# pycom_weather_station_pcb.net
KiCad netlist of a schematic drawn in EAGLE
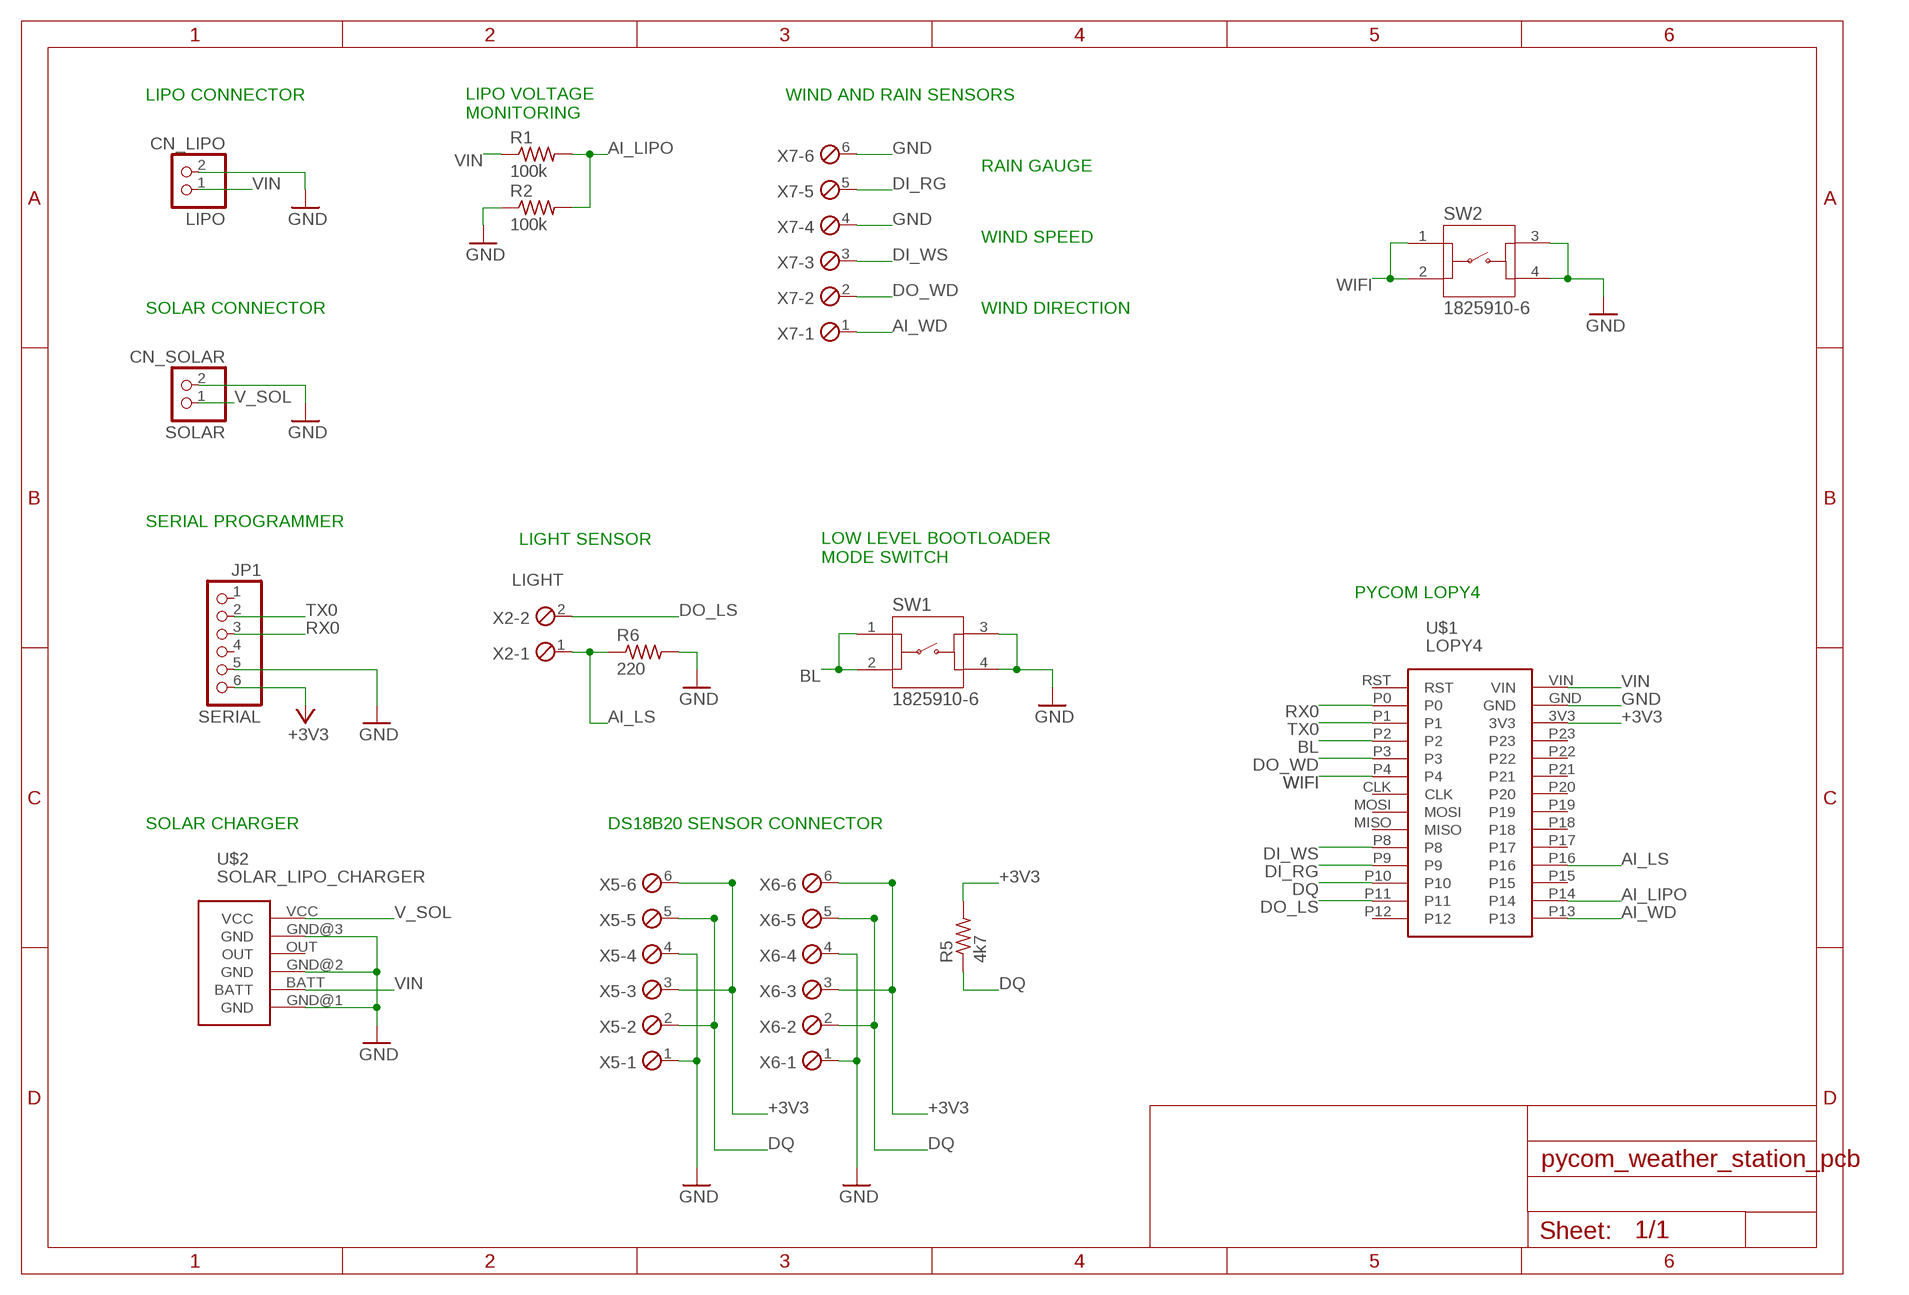
[diagram p0: schematic, sheet 1]

(export (version "E")
  (design (tool "Eeschema 10.0.6"))
  (components
    (comp (ref "CN_LIPO")
      (value "LIPO")
      (footprint "eagle-import:JST-PH-2-THM")
      (libsource (lib "eagle-import") (part "JST_2PIN-THM"))
    )
    (comp (ref "CN_SOLAR")
      (value "SOLAR")
      (footprint "eagle-import:JST-PH-2-THM")
      (libsource (lib "eagle-import") (part "adafruit_420_JST_2PIN-THM"))
    )
    (comp (ref "JP1")
      (value "SERIAL")
      (footprint "eagle-import:1X06-CLEANBIG")
      (libsource (lib "eagle-import") (part "PINHD-1X6CB"))
    )
    (comp (ref "R1")
      (value "100k")
      (footprint "eagle-import:0204_7")
      (libsource (lib "eagle-import") (part "R-US_0204/7"))
    )
    (comp (ref "R2")
      (value "100k")
      (footprint "eagle-import:0204_7")
      (libsource (lib "eagle-import") (part "R-US_0204/7"))
    )
    (comp (ref "R5")
      (value "4k7")
      (footprint "eagle-import:0204_7")
      (libsource (lib "eagle-import") (part "R-US_0204/7"))
    )
    (comp (ref "R6")
      (value "220")
      (footprint "eagle-import:0204_7")
      (libsource (lib "eagle-import") (part "R-US_0204/7"))
    )
    (comp (ref "SW1")
      (value "1825910-6")
      (footprint "eagle-import:SW_1825910-6-4")
      (fields (field (name "MANUFACTURER") "TE CONNECTIVITY"))
      (libsource (lib "eagle-import") (part "1825910-6"))
    )
    (comp (ref "SW2")
      (value "1825910-6")
      (footprint "eagle-import:SW_1825910-6-4")
      (fields (field (name "MANUFACTURER") "TE CONNECTIVITY"))
      (libsource (lib "eagle-import") (part "1825910-6"))
    )
    (comp (ref "U$1")
      (value "LOPY4")
      (footprint "eagle-import:LOPY4")
      (libsource (lib "eagle-import") (part "LOPY4"))
    )
    (comp (ref "U$2")
      (value "SOLAR_LIPO_CHARGER")
      (footprint "eagle-import:SOLAR_LIPO_CHARGER")
      (libsource (lib "eagle-import") (part "SOLAR_LIPO_CHARGER"))
    )
    (comp (ref "X2")
      (value "LIGHT")
      (footprint "eagle-import:2POL254")
      (libsource (lib "eagle-import") (part "MPT2"))
    )
    (comp (ref "X5")
      (value "MPT6")
      (footprint "eagle-import:6POL254")
      (libsource (lib "eagle-import") (part "MPT6"))
    )
    (comp (ref "X6")
      (value "MPT6")
      (footprint "eagle-import:6POL254")
      (libsource (lib "eagle-import") (part "MPT6"))
    )
    (comp (ref "X7")
      (value "MPT6")
      (footprint "eagle-import:6POL254")
      (libsource (lib "eagle-import") (part "MPT6"))
    )
  )
  (nets
    (net (code "1") (name "+3V3") (class "Default")
      (node (ref "JP1") (pin "6") (pinfunction "6_6") (pintype "passive"))
      (node (ref "R5") (pin "2") (pinfunction "2_2") (pintype "passive"))
      (node (ref "U$1") (pin "3V3") (pinfunction "3V3_3V3") (pintype "bidirectional"))
      (node (ref "X5") (pin "3") (pinfunction "1_3") (pintype "passive"))
      (node (ref "X5") (pin "6") (pinfunction "1_6") (pintype "passive"))
      (node (ref "X6") (pin "3") (pinfunction "1_3") (pintype "passive"))
      (node (ref "X6") (pin "6") (pinfunction "1_6") (pintype "passive"))
    )
    (net (code "2") (name "/AI_LIPO") (class "Default")
      (node (ref "R1") (pin "2") (pinfunction "2_2") (pintype "passive"))
      (node (ref "R2") (pin "2") (pinfunction "2_2") (pintype "passive"))
      (node (ref "U$1") (pin "P14") (pinfunction "P14_P14") (pintype "bidirectional"))
    )
    (net (code "3") (name "/AI_LS") (class "Default")
      (node (ref "R6") (pin "1") (pinfunction "1_1") (pintype "passive"))
      (node (ref "U$1") (pin "P16") (pinfunction "P16_P16") (pintype "bidirectional"))
      (node (ref "X2") (pin "1") (pinfunction "1_1") (pintype "passive"))
    )
    (net (code "4") (name "/AI_WD") (class "Default")
      (node (ref "U$1") (pin "P13") (pinfunction "P13_P13") (pintype "bidirectional"))
      (node (ref "X7") (pin "1") (pinfunction "1_1") (pintype "passive"))
    )
    (net (code "5") (name "/BL") (class "Default")
      (node (ref "SW1") (pin "1") (pinfunction "1_1") (pintype "passive"))
      (node (ref "SW1") (pin "2") (pinfunction "2_2") (pintype "passive"))
      (node (ref "U$1") (pin "P2") (pinfunction "P2_P2") (pintype "bidirectional"))
    )
    (net (code "6") (name "/DI_RG") (class "Default")
      (node (ref "U$1") (pin "P9") (pinfunction "P9_P9") (pintype "bidirectional"))
      (node (ref "X7") (pin "5") (pinfunction "1_5") (pintype "passive"))
    )
    (net (code "7") (name "/DI_WS") (class "Default")
      (node (ref "U$1") (pin "P8") (pinfunction "P8_P8") (pintype "bidirectional"))
      (node (ref "X7") (pin "3") (pinfunction "1_3") (pintype "passive"))
    )
    (net (code "8") (name "/DO_LS") (class "Default")
      (node (ref "U$1") (pin "P11") (pinfunction "P11_P11") (pintype "bidirectional"))
      (node (ref "X2") (pin "2") (pinfunction "1_2") (pintype "passive"))
    )
    (net (code "9") (name "/DO_WD") (class "Default")
      (node (ref "U$1") (pin "P3") (pinfunction "P3_P3") (pintype "bidirectional"))
      (node (ref "X7") (pin "2") (pinfunction "1_2") (pintype "passive"))
    )
    (net (code "10") (name "/DQ") (class "Default")
      (node (ref "R5") (pin "1") (pinfunction "1_1") (pintype "passive"))
      (node (ref "U$1") (pin "P10") (pinfunction "P10_P10") (pintype "bidirectional"))
      (node (ref "X5") (pin "2") (pinfunction "1_2") (pintype "passive"))
      (node (ref "X5") (pin "5") (pinfunction "1_5") (pintype "passive"))
      (node (ref "X6") (pin "2") (pinfunction "1_2") (pintype "passive"))
      (node (ref "X6") (pin "5") (pinfunction "1_5") (pintype "passive"))
    )
    (net (code "11") (name "/RX0") (class "Default")
      (node (ref "JP1") (pin "3") (pinfunction "3_3") (pintype "passive"))
      (node (ref "U$1") (pin "P0") (pinfunction "P0_P0") (pintype "bidirectional"))
    )
    (net (code "12") (name "/TX0") (class "Default")
      (node (ref "JP1") (pin "2") (pinfunction "2_2") (pintype "passive"))
      (node (ref "U$1") (pin "P1") (pinfunction "P1_P1") (pintype "bidirectional"))
    )
    (net (code "13") (name "/VIN") (class "Default")
      (node (ref "CN_LIPO") (pin "1") (pinfunction "2_1") (pintype "passive"))
      (node (ref "R1") (pin "1") (pinfunction "1_1") (pintype "passive"))
      (node (ref "U$1") (pin "VIN") (pinfunction "VIN_VIN") (pintype "bidirectional"))
      (node (ref "U$2") (pin "BATT") (pinfunction "BATT_BATT") (pintype "bidirectional"))
    )
    (net (code "14") (name "/V_SOL") (class "Default")
      (node (ref "CN_SOLAR") (pin "1") (pinfunction "2_1") (pintype "passive"))
      (node (ref "U$2") (pin "VCC") (pinfunction "VCC_VCC") (pintype "bidirectional"))
    )
    (net (code "15") (name "/WIFI") (class "Default")
      (node (ref "SW2") (pin "1") (pinfunction "1_1") (pintype "passive"))
      (node (ref "SW2") (pin "2") (pinfunction "2_2") (pintype "passive"))
      (node (ref "U$1") (pin "P4") (pinfunction "P4_P4") (pintype "bidirectional"))
    )
    (net (code "16") (name "GND") (class "Default")
      (node (ref "CN_LIPO") (pin "2") (pinfunction "1_2") (pintype "passive"))
      (node (ref "CN_SOLAR") (pin "2") (pinfunction "1_2") (pintype "passive"))
      (node (ref "JP1") (pin "5") (pinfunction "5_5") (pintype "passive"))
      (node (ref "R2") (pin "1") (pinfunction "1_1") (pintype "passive"))
      (node (ref "R6") (pin "2") (pinfunction "2_2") (pintype "passive"))
      (node (ref "SW1") (pin "3") (pinfunction "3_3") (pintype "passive"))
      (node (ref "SW1") (pin "4") (pinfunction "4_4") (pintype "passive"))
      (node (ref "SW2") (pin "3") (pinfunction "3_3") (pintype "passive"))
      (node (ref "SW2") (pin "4") (pinfunction "4_4") (pintype "passive"))
      (node (ref "U$1") (pin "GND") (pinfunction "GND_GND") (pintype "bidirectional"))
      (node (ref "U$2") (pin "GND@1") (pinfunction "GND_GND@1") (pintype "bidirectional"))
      (node (ref "U$2") (pin "GND@2") (pinfunction "GND_GND@2") (pintype "bidirectional"))
      (node (ref "U$2") (pin "GND@3") (pinfunction "GND_GND@3") (pintype "bidirectional"))
      (node (ref "X5") (pin "1") (pinfunction "1_1") (pintype "passive"))
      (node (ref "X5") (pin "4") (pinfunction "1_4") (pintype "passive"))
      (node (ref "X6") (pin "1") (pinfunction "1_1") (pintype "passive"))
      (node (ref "X6") (pin "4") (pinfunction "1_4") (pintype "passive"))
      (node (ref "X7") (pin "4") (pinfunction "1_4") (pintype "passive"))
      (node (ref "X7") (pin "6") (pinfunction "1_6") (pintype "passive"))
    )
    (net (code "17") (name "unconnected-(JP1-Pad1)") (class "Default")
      (node (ref "JP1") (pin "1") (pinfunction "1_1") (pintype "passive"))
    )
    (net (code "18") (name "unconnected-(JP1-Pad4)") (class "Default")
      (node (ref "JP1") (pin "4") (pinfunction "4_4") (pintype "passive"))
    )
    (net (code "19") (name "unconnected-(U$1-PadCLK)") (class "Default")
      (node (ref "U$1") (pin "CLK") (pinfunction "CLK_CLK") (pintype "bidirectional"))
    )
    (net (code "20") (name "unconnected-(U$1-PadMISO)") (class "Default")
      (node (ref "U$1") (pin "MISO") (pinfunction "MISO_MISO") (pintype "bidirectional"))
    )
    (net (code "21") (name "unconnected-(U$1-PadMOSI)") (class "Default")
      (node (ref "U$1") (pin "MOSI") (pinfunction "MOSI_MOSI") (pintype "bidirectional"))
    )
    (net (code "22") (name "unconnected-(U$1-PadP12)") (class "Default")
      (node (ref "U$1") (pin "P12") (pinfunction "P12_P12") (pintype "bidirectional"))
    )
    (net (code "23") (name "unconnected-(U$1-PadP15)") (class "Default")
      (node (ref "U$1") (pin "P15") (pinfunction "P15_P15") (pintype "bidirectional"))
    )
    (net (code "24") (name "unconnected-(U$1-PadP17)") (class "Default")
      (node (ref "U$1") (pin "P17") (pinfunction "P17_P17") (pintype "bidirectional"))
    )
    (net (code "25") (name "unconnected-(U$1-PadP18)") (class "Default")
      (node (ref "U$1") (pin "P18") (pinfunction "P18_P18") (pintype "bidirectional"))
    )
    (net (code "26") (name "unconnected-(U$1-PadP19)") (class "Default")
      (node (ref "U$1") (pin "P19") (pinfunction "P19_P19") (pintype "bidirectional"))
    )
    (net (code "27") (name "unconnected-(U$1-PadP20)") (class "Default")
      (node (ref "U$1") (pin "P20") (pinfunction "P20_P20") (pintype "bidirectional"))
    )
    (net (code "28") (name "unconnected-(U$1-PadP21)") (class "Default")
      (node (ref "U$1") (pin "P21") (pinfunction "P21_P21") (pintype "bidirectional"))
    )
    (net (code "29") (name "unconnected-(U$1-PadP22)") (class "Default")
      (node (ref "U$1") (pin "P22") (pinfunction "P22_P22") (pintype "bidirectional"))
    )
    (net (code "30") (name "unconnected-(U$1-PadP23)") (class "Default")
      (node (ref "U$1") (pin "P23") (pinfunction "P23_P23") (pintype "bidirectional"))
    )
    (net (code "31") (name "unconnected-(U$1-PadRST)") (class "Default")
      (node (ref "U$1") (pin "RST") (pinfunction "RST_RST") (pintype "bidirectional"))
    )
    (net (code "32") (name "unconnected-(U$2-PadOUT)") (class "Default")
      (node (ref "U$2") (pin "OUT") (pinfunction "OUT_OUT") (pintype "bidirectional"))
    )
  )
)
